# OnOnfre_DevBoard.net
KiCad netlist of a schematic drawn in EAGLE
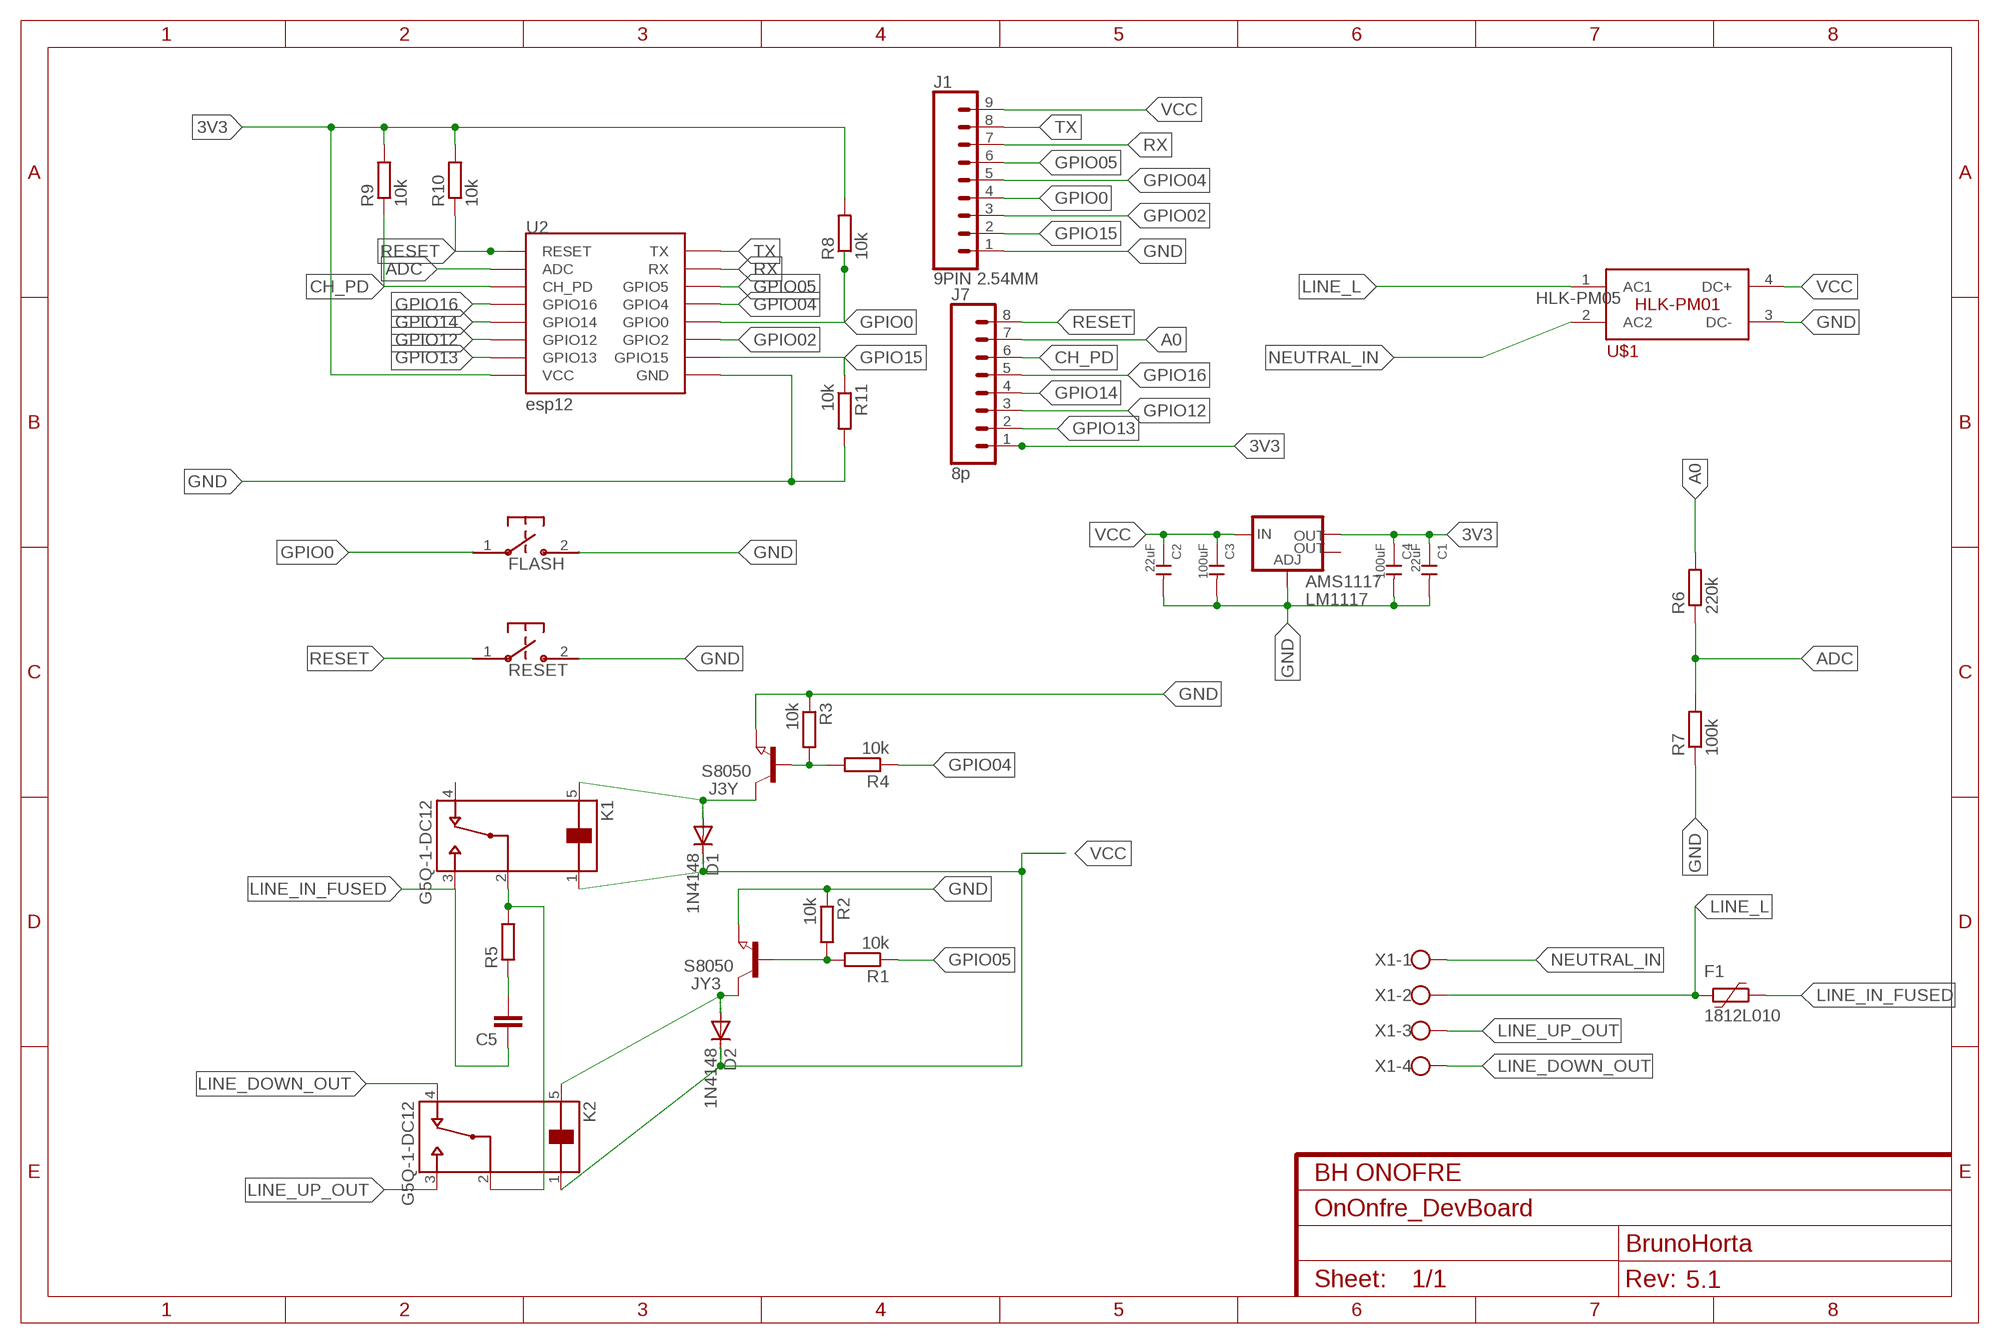
[diagram p0: schematic, sheet 1]

(export (version "E")
  (design (tool "Eeschema 10.0.6"))
  (components
    (comp (ref "AMS1117")
      (value "LM1117")
      (footprint "eagle-import:SOT223")
      (libsource (lib "eagle-import") (part "V_REG_LM1117SOT223"))
    )
    (comp (ref "C1")
      (value "22uF")
      (footprint "eagle-import:C1206")
      (fields (field (name "MPN") "CC1206KKX7RCBB102"))
      (libsource (lib "eagle-import") (part "CERAMIC-1NF-1KV-10%-X7R?(1206)"))
    )
    (comp (ref "C2")
      (value "22uF")
      (footprint "eagle-import:C1206")
      (fields (field (name "MPN") "CC1206KKX7RCBB102"))
      (libsource (lib "eagle-import") (part "CERAMIC-1NF-1KV-10%-X7R?(1206)"))
    )
    (comp (ref "C3")
      (value "100uF")
      (footprint "eagle-import:C1206")
      (fields (field (name "MPN") "CC1206KKX7RCBB102"))
      (libsource (lib "eagle-import") (part "CERAMIC-1NF-1KV-10%-X7R?(1206)"))
    )
    (comp (ref "C4")
      (value "100uF")
      (footprint "eagle-import:C1206")
      (fields (field (name "MPN") "CC1206KKX7RCBB102"))
      (libsource (lib "eagle-import") (part "CERAMIC-1NF-1KV-10%-X7R?(1206)"))
    )
    (comp (ref "C5")
      (value "C-EU102-043X133")
      (footprint "eagle-import:C102-043X133")
      (libsource (lib "eagle-import") (part "C-EU102-043X133"))
    )
    (comp (ref "D1")
      (value "1N4148")
      (footprint "eagle-import:SOD80C")
      (libsource (lib "eagle-import") (part "DIODE-SOD80C"))
    )
    (comp (ref "D2")
      (value "1N4148")
      (footprint "eagle-import:SOD80C")
      (libsource (lib "eagle-import") (part "DIODE-SOD80C"))
    )
    (comp (ref "F1")
      (value "1812L010")
      (footprint "eagle-import:1812L")
      (fields (field (name "MF") "Littelfuse"))
      (libsource (lib "eagle-import") (part "?1812L010"))
    )
    (comp (ref "FLASH")
      (value "B3U-1000P-2P-SMD")
      (footprint "eagle-import:B3U-1000P")
      (fields (field (name "MANUFACTURER") "Omron") (field (name "MPN") "B3U-1000P"))
      (libsource (lib "eagle-import") (part "B3U-1000P"))
    )
    (comp (ref "J1")
      (value "9PIN 2.54MM")
      (footprint "eagle-import:1X09")
      (libsource (lib "eagle-import") (part "CONN_09"))
    )
    (comp (ref "J3Y")
      (value "S8050")
      (footprint "eagle-import:SOT23")
      (libsource (lib "eagle-import") (part "NPN-TRANSISTOR_SOT23"))
    )
    (comp (ref "J7")
      (value "8p")
      (footprint "eagle-import:1X08")
      (libsource (lib "eagle-import") (part "CONN_08{dblquote}"))
    )
    (comp (ref "JY3")
      (value "S8050")
      (footprint "eagle-import:SOT23")
      (libsource (lib "eagle-import") (part "NPN-TRANSISTOR_SOT23"))
    )
    (comp (ref "K1")
      (value "G5Q-1-DC12")
      (footprint "eagle-import:RELAY_G5Q-1-DC12")
      (fields (field (name "MF") "Omron"))
      (libsource (lib "eagle-import") (part "G5Q-1-DC12"))
    )
    (comp (ref "K2")
      (value "G5Q-1-DC12")
      (footprint "eagle-import:RELAY_G5Q-1-DC12")
      (fields (field (name "MF") "Omron"))
      (libsource (lib "eagle-import") (part "G5Q-1-DC12"))
    )
    (comp (ref "R1")
      (value "10k")
      (footprint "eagle-import:R0603")
      (libsource (lib "eagle-import") (part "R-EU_R0603"))
    )
    (comp (ref "R2")
      (value "10k")
      (footprint "eagle-import:R0603")
      (libsource (lib "eagle-import") (part "R-EU_R0603"))
    )
    (comp (ref "R3")
      (value "10k")
      (footprint "eagle-import:R0603")
      (libsource (lib "eagle-import") (part "R-EU_R0603"))
    )
    (comp (ref "R4")
      (value "10k")
      (footprint "eagle-import:R0603")
      (libsource (lib "eagle-import") (part "R-EU_R0603"))
    )
    (comp (ref "R5")
      (value "R-EU_R2512")
      (footprint "eagle-import:R2512")
      (libsource (lib "eagle-import") (part "R-EU_R2512"))
    )
    (comp (ref "R6")
      (value "220k")
      (footprint "eagle-import:R0603")
      (libsource (lib "eagle-import") (part "R-EU_R0603"))
    )
    (comp (ref "R7")
      (value "100k")
      (footprint "eagle-import:R0603")
      (libsource (lib "eagle-import") (part "R-EU_R0603"))
    )
    (comp (ref "R8")
      (value "10k")
      (footprint "eagle-import:R0603")
      (libsource (lib "eagle-import") (part "R-EU_R0603"))
    )
    (comp (ref "R9")
      (value "10k")
      (footprint "eagle-import:R0603")
      (libsource (lib "eagle-import") (part "R-EU_R0603"))
    )
    (comp (ref "R10")
      (value "10k")
      (footprint "eagle-import:R0603")
      (libsource (lib "eagle-import") (part "R-EU_R0603"))
    )
    (comp (ref "R11")
      (value "10k")
      (footprint "eagle-import:R0603")
      (libsource (lib "eagle-import") (part "R-EU_R0603"))
    )
    (comp (ref "RESET")
      (value "B3U-1000P-2P-SMD")
      (footprint "eagle-import:B3U-1000P")
      (fields (field (name "MANUFACTURER") "Omron") (field (name "MPN") "B3U-1000P"))
      (libsource (lib "eagle-import") (part "B3U-1000P"))
    )
    (comp (ref "U$1")
      (value "HLK-PM01")
      (footprint "eagle-import:HLK-PM01")
      (fields (field (name "MF") "Hi-link") (field (name "MP") "hlk-pm01"))
      (libsource (lib "eagle-import") (part "HLK-PM01"))
    )
    (comp (ref "U2")
      (value "esp12")
      (footprint "eagle-import:ESP12-SMD")
      (libsource (lib "eagle-import") (part "ESP12SMD"))
    )
    (comp (ref "X1")
      (value "W237-4")
      (footprint "eagle-import:W237-4")
      (libsource (lib "eagle-import") (part "W237-4"))
    )
  )
  (nets
    (net (code "1") (name "3V3") (class "Default")
      (node (ref "AMS1117") (pin "2") (pinfunction "OUT_2") (pintype "output"))
      (node (ref "C1") (pin "1") (pinfunction "1_1") (pintype "passive"))
      (node (ref "C4") (pin "1") (pinfunction "1_1") (pintype "passive"))
      (node (ref "J7") (pin "1") (pinfunction "1_1") (pintype "passive"))
      (node (ref "R10") (pin "2") (pinfunction "2_2") (pintype "passive"))
      (node (ref "R8") (pin "2") (pinfunction "2_2") (pintype "passive"))
      (node (ref "R9") (pin "2") (pinfunction "2_2") (pintype "passive"))
      (node (ref "U2") (pin "VCC") (pinfunction "VCC_VCC") (pintype "bidirectional"))
    )
    (net (code "2") (name "A0") (class "Default")
      (node (ref "J7") (pin "7") (pinfunction "7_7") (pintype "passive"))
      (node (ref "R6") (pin "2") (pinfunction "2_2") (pintype "passive"))
    )
    (net (code "3") (name "ADC") (class "Default")
      (node (ref "R6") (pin "1") (pinfunction "1_1") (pintype "passive"))
      (node (ref "R7") (pin "2") (pinfunction "2_2") (pintype "passive"))
      (node (ref "U2") (pin "ADC") (pinfunction "ADC_ADC") (pintype "bidirectional"))
    )
    (net (code "4") (name "CH_PD") (class "Default")
      (node (ref "J7") (pin "6") (pinfunction "6_6") (pintype "passive"))
      (node (ref "R9") (pin "1") (pinfunction "1_1") (pintype "passive"))
      (node (ref "U2") (pin "CH_PD") (pinfunction "CH_PD_CH_PD") (pintype "bidirectional"))
    )
    (net (code "5") (name "GND") (class "Default")
      (node (ref "AMS1117") (pin "1") (pinfunction "ADJ_1") (pintype "input"))
      (node (ref "C1") (pin "2") (pinfunction "2_2") (pintype "passive"))
      (node (ref "C2") (pin "2") (pinfunction "2_2") (pintype "passive"))
      (node (ref "C3") (pin "2") (pinfunction "2_2") (pintype "passive"))
      (node (ref "C4") (pin "2") (pinfunction "2_2") (pintype "passive"))
      (node (ref "FLASH") (pin "2") (pinfunction "P$2_2") (pintype "passive"))
      (node (ref "J1") (pin "1") (pinfunction "1_1") (pintype "passive"))
      (node (ref "J3Y") (pin "2") (pinfunction "E_2") (pintype "passive"))
      (node (ref "JY3") (pin "2") (pinfunction "E_2") (pintype "passive"))
      (node (ref "R11") (pin "2") (pinfunction "2_2") (pintype "passive"))
      (node (ref "R2") (pin "1") (pinfunction "1_1") (pintype "passive"))
      (node (ref "R3") (pin "1") (pinfunction "1_1") (pintype "passive"))
      (node (ref "R7") (pin "1") (pinfunction "1_1") (pintype "passive"))
      (node (ref "RESET") (pin "2") (pinfunction "P$2_2") (pintype "passive"))
      (node (ref "U$1") (pin "3") (pinfunction "DC-_3") (pintype "power_in"))
      (node (ref "U2") (pin "GND") (pinfunction "GND_GND") (pintype "bidirectional"))
    )
    (net (code "6") (name "GPIO0") (class "Default")
      (node (ref "FLASH") (pin "1") (pinfunction "P$1_1") (pintype "passive"))
      (node (ref "J1") (pin "4") (pinfunction "4_4") (pintype "passive"))
      (node (ref "R8") (pin "1") (pinfunction "1_1") (pintype "passive"))
      (node (ref "U2") (pin "GPIO0") (pinfunction "GPIO0_GPIO0") (pintype "bidirectional"))
    )
    (net (code "7") (name "GPIO02") (class "Default")
      (node (ref "J1") (pin "3") (pinfunction "3_3") (pintype "passive"))
      (node (ref "U2") (pin "GPIO2") (pinfunction "GPIO2_GPIO2") (pintype "bidirectional"))
    )
    (net (code "8") (name "GPIO04") (class "Default")
      (node (ref "J1") (pin "5") (pinfunction "5_5") (pintype "passive"))
      (node (ref "R4") (pin "1") (pinfunction "1_1") (pintype "passive"))
      (node (ref "U2") (pin "GPIO4") (pinfunction "GPIO4_GPIO4") (pintype "bidirectional"))
    )
    (net (code "9") (name "GPIO05") (class "Default")
      (node (ref "J1") (pin "6") (pinfunction "6_6") (pintype "passive"))
      (node (ref "R1") (pin "1") (pinfunction "1_1") (pintype "passive"))
      (node (ref "U2") (pin "GPIO5") (pinfunction "GPIO5_GPIO5") (pintype "bidirectional"))
    )
    (net (code "10") (name "GPIO12") (class "Default")
      (node (ref "J7") (pin "3") (pinfunction "3_3") (pintype "passive"))
      (node (ref "U2") (pin "GPIO12") (pinfunction "GPIO12_GPIO12") (pintype "bidirectional"))
    )
    (net (code "11") (name "GPIO13") (class "Default")
      (node (ref "J7") (pin "2") (pinfunction "2_2") (pintype "passive"))
      (node (ref "U2") (pin "GPIO13") (pinfunction "GPIO13_GPIO13") (pintype "bidirectional"))
    )
    (net (code "12") (name "GPIO14") (class "Default")
      (node (ref "J7") (pin "4") (pinfunction "4_4") (pintype "passive"))
      (node (ref "U2") (pin "GPIO14") (pinfunction "GPIO14_GPIO14") (pintype "bidirectional"))
    )
    (net (code "13") (name "GPIO15") (class "Default")
      (node (ref "J1") (pin "2") (pinfunction "2_2") (pintype "passive"))
      (node (ref "R11") (pin "1") (pinfunction "1_1") (pintype "passive"))
      (node (ref "U2") (pin "GPIO15") (pinfunction "GPIO15_GPIO15") (pintype "bidirectional"))
    )
    (net (code "14") (name "GPIO16") (class "Default")
      (node (ref "J7") (pin "5") (pinfunction "5_5") (pintype "passive"))
      (node (ref "U2") (pin "GPIO16") (pinfunction "GPIO16_GPIO16") (pintype "bidirectional"))
    )
    (net (code "15") (name "LINE_DOWN_OUT") (class "Default")
      (node (ref "K2") (pin "4") (pinfunction "4_4") (pintype "passive"))
      (node (ref "X1") (pin "4") (pinfunction "KL_4") (pintype "passive"))
    )
    (net (code "16") (name "LINE_IN_FUSED") (class "Default")
      (node (ref "C5") (pin "1") (pinfunction "1_1") (pintype "passive"))
      (node (ref "F1") (pin "1") (pinfunction "1_1") (pintype "passive"))
      (node (ref "K1") (pin "3") (pinfunction "3_3") (pintype "passive"))
    )
    (net (code "17") (name "LINE_L") (class "Default")
      (node (ref "F1") (pin "2") (pinfunction "2_2") (pintype "passive"))
      (node (ref "U$1") (pin "1") (pinfunction "AC1_1") (pintype "power_in"))
      (node (ref "X1") (pin "2") (pinfunction "KL_2") (pintype "passive"))
    )
    (net (code "18") (name "LINE_UP_OUT") (class "Default")
      (node (ref "K2") (pin "3") (pinfunction "3_3") (pintype "passive"))
      (node (ref "X1") (pin "3") (pinfunction "KL_3") (pintype "passive"))
    )
    (net (code "19") (name "NEUTRAL_IN") (class "Default")
      (node (ref "U$1") (pin "2") (pinfunction "AC2_2") (pintype "power_in"))
      (node (ref "X1") (pin "1") (pinfunction "KL_1") (pintype "passive"))
    )
    (net (code "20") (name "Net-(C5-Pad2)") (class "Default")
      (node (ref "C5") (pin "2") (pinfunction "2_2") (pintype "passive"))
      (node (ref "R5") (pin "1") (pinfunction "1_1") (pintype "passive"))
    )
    (net (code "21") (name "Net-(J3Y-B)") (class "Default")
      (node (ref "J3Y") (pin "1") (pinfunction "B_1") (pintype "passive"))
      (node (ref "R3") (pin "2") (pinfunction "2_2") (pintype "passive"))
      (node (ref "R4") (pin "2") (pinfunction "2_2") (pintype "passive"))
    )
    (net (code "22") (name "Net-(J3Y-C)") (class "Default")
      (node (ref "D1") (pin "A") (pinfunction "A_A") (pintype "passive"))
      (node (ref "J3Y") (pin "3") (pinfunction "C_3") (pintype "passive"))
      (node (ref "K1") (pin "5") (pinfunction "5_5") (pintype "passive"))
    )
    (net (code "23") (name "Net-(JY3-B)") (class "Default")
      (node (ref "JY3") (pin "1") (pinfunction "B_1") (pintype "passive"))
      (node (ref "R1") (pin "2") (pinfunction "2_2") (pintype "passive"))
      (node (ref "R2") (pin "2") (pinfunction "2_2") (pintype "passive"))
    )
    (net (code "24") (name "Net-(JY3-C)") (class "Default")
      (node (ref "D2") (pin "A") (pinfunction "A_A") (pintype "passive"))
      (node (ref "JY3") (pin "3") (pinfunction "C_3") (pintype "passive"))
      (node (ref "K2") (pin "5") (pinfunction "5_5") (pintype "passive"))
    )
    (net (code "25") (name "Net-(K1-Pad2)") (class "Default")
      (node (ref "K1") (pin "2") (pinfunction "2_2") (pintype "passive"))
      (node (ref "K2") (pin "2") (pinfunction "2_2") (pintype "passive"))
      (node (ref "R5") (pin "2") (pinfunction "2_2") (pintype "passive"))
    )
    (net (code "26") (name "RESET") (class "Default")
      (node (ref "J7") (pin "8") (pinfunction "8_8") (pintype "passive"))
      (node (ref "R10") (pin "1") (pinfunction "1_1") (pintype "passive"))
      (node (ref "RESET") (pin "1") (pinfunction "P$1_1") (pintype "passive"))
      (node (ref "U2") (pin "RESET") (pinfunction "RESET_RESET") (pintype "bidirectional"))
    )
    (net (code "27") (name "RX") (class "Default")
      (node (ref "J1") (pin "7") (pinfunction "7_7") (pintype "passive"))
      (node (ref "U2") (pin "RXD0") (pinfunction "RX_RXD0") (pintype "bidirectional"))
    )
    (net (code "28") (name "TX") (class "Default")
      (node (ref "J1") (pin "8") (pinfunction "8_8") (pintype "passive"))
      (node (ref "U2") (pin "TXD0") (pinfunction "TX_TXD0") (pintype "bidirectional"))
    )
    (net (code "29") (name "VCC") (class "Default")
      (node (ref "AMS1117") (pin "3") (pinfunction "IN_3") (pintype "input"))
      (node (ref "C2") (pin "1") (pinfunction "1_1") (pintype "passive"))
      (node (ref "C3") (pin "1") (pinfunction "1_1") (pintype "passive"))
      (node (ref "D1") (pin "C") (pinfunction "C_C") (pintype "passive"))
      (node (ref "D2") (pin "C") (pinfunction "C_C") (pintype "passive"))
      (node (ref "J1") (pin "9") (pinfunction "9_9") (pintype "passive"))
      (node (ref "K1") (pin "1") (pinfunction "1_1") (pintype "passive"))
      (node (ref "K2") (pin "1") (pinfunction "1_1") (pintype "passive"))
      (node (ref "U$1") (pin "4") (pinfunction "DC+_4") (pintype "power_in"))
    )
    (net (code "30") (name "unconnected-(AMS1117-OUT-Pad4)") (class "Default")
      (node (ref "AMS1117") (pin "4") (pinfunction "OUT_4") (pintype "output"))
    )
    (net (code "31") (name "unconnected-(K1-Pad4)") (class "Default")
      (node (ref "K1") (pin "4") (pinfunction "4_4") (pintype "passive"))
    )
  )
)
